# LMR514205V.net
KiCad netlist of a schematic drawn in Altium Designer
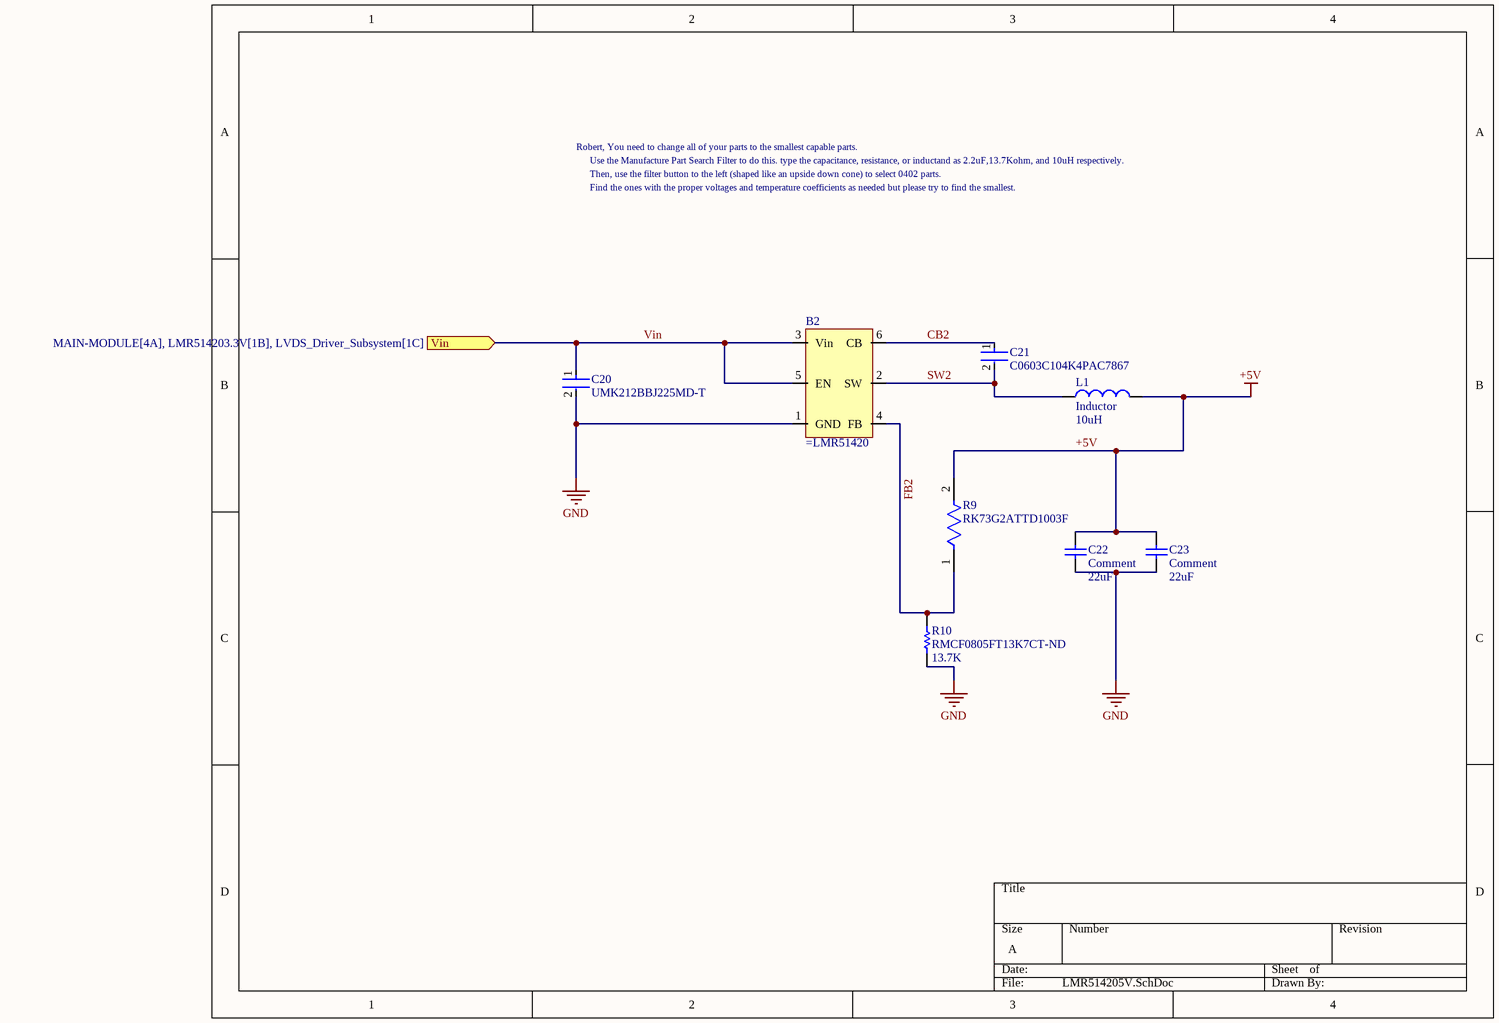
[diagram p0: LMR514205V.SchDoc]

(export (version "E")
  (design (tool "Eeschema 10.0.6"))
  (components
    (comp (ref "B2") (value "~") (footprint "LMR51420IC") (libsource (lib "LMR51420") (part "Component_1")))
    (comp (ref "C20")
      (value "UMK212BBJ225MD-T")
      (footprint "FP-0805-L_2_0_0_2-W_1_25-IPC_A")
      (description "Multilayer Ceramic Capacitor 2.2uF 50V X5R 20% SMD 0803 T/R")
      (fields (field (name "TOLERANCE") "20%"))
      (libsource (lib "Altium Content Vault") (part "02cd4be3c70576c341d710602a673aa"))
    )
    (comp (ref "C21")
      (value "C0603C104K4PAC7867")
      (footprint "CAP CER 0.1UF 16V X7R 0603")
      (description "CAP CER 0.1UF 16V X5R 0603")
      (fields
        (field (name "OCTOPART") "https://octopart.com/c0603c104k4pactu-kemet-12592163")
        (field (name "MANUFACTURER") "KEMET")
      )
      (libsource (lib "Miscellaneous Devices") (part "b4654b650e69147ec39a6b967a45e02"))
    )
    (comp (ref "C22")
      (value "Comment")
      (footprint "Cap22uF_C1206C226M4PAC7800")
      (description "Capacitor")
      (fields (field (name "ALTIUM_VALUE") "22uF") (field (name "PUBLISHER") "Altium Limited"))
      (libsource (lib "Miscellaneous Devices") (part "Cap"))
    )
    (comp (ref "C23")
      (value "Comment")
      (footprint "Cap22uF_C1206C226M4PAC7800")
      (description "Capacitor")
      (fields (field (name "ALTIUM_VALUE") "22uF") (field (name "PUBLISHER") "Altium Limited"))
      (libsource (lib "Miscellaneous Devices") (part "Cap"))
    )
    (comp (ref "L1")
      (value "Inductor")
      (footprint "MSS1246H-103MED 10uH")
      (fields (field (name "ALTIUM_VALUE") "10uH") (field (name "PUBLISHER") "Altium Limited"))
      (libsource (lib "Miscellaneous Devices") (part "Inductor"))
    )
    (comp (ref "R9")
      (value "RK73G2ATTD1003F")
      (footprint "FP-RK73G2A-IPC_A")
      (description "100kΩ ±1% 0.125W Chip Resistor 0805 Thick Film AEC-Q200 Qualified")
      (fields (field (name "TOLERANCE") "1%"))
      (libsource (lib "Altium Content Vault") (part "1029c3af85768c4190bb7ad29bc67b5"))
    )
    (comp (ref "R10")
      (value "RMCF0805FT13K7CT-ND")
      (footprint "RMCF0805FT13K7_13.7k")
      (description "Resistor")
      (fields (field (name "ALTIUM_VALUE") "13.7K") (field (name "PUBLISHER") "Altium Limited"))
      (libsource (lib "Miscellaneous Devices") (part "Res1"))
    )
  )
  (nets
    (net (code "1") (name "+5V") (class "Default")
      (node (ref "C22") (pin "2") (pinfunction "2_2") (pintype "passive"))
      (node (ref "C23") (pin "2") (pinfunction "2_2") (pintype "passive"))
      (node (ref "L1") (pin "2") (pinfunction "2_2") (pintype "passive"))
      (node (ref "R9") (pin "2") (pinfunction "2_2") (pintype "passive"))
    )
    (net (code "2") (name "/CB2") (class "Default")
      (node (ref "B2") (pin "6") (pinfunction "CB_6") (pintype "passive"))
      (node (ref "C21") (pin "1") (pinfunction "1_1") (pintype "passive"))
    )
    (net (code "3") (name "/FB2") (class "Default")
      (node (ref "B2") (pin "4") (pinfunction "FB_4") (pintype "passive"))
      (node (ref "R10") (pin "2") (pinfunction "2_2") (pintype "passive"))
      (node (ref "R9") (pin "1") (pinfunction "1_1") (pintype "passive"))
    )
    (net (code "4") (name "/SW2") (class "Default")
      (node (ref "B2") (pin "2") (pinfunction "SW_2") (pintype "passive"))
      (node (ref "C21") (pin "2") (pinfunction "2_2") (pintype "passive"))
      (node (ref "L1") (pin "1") (pinfunction "1_1") (pintype "passive"))
    )
    (net (code "5") (name "/Vin") (class "Default")
      (node (ref "B2") (pin "3") (pinfunction "Vin_3") (pintype "passive"))
      (node (ref "B2") (pin "5") (pinfunction "EN_5") (pintype "passive"))
      (node (ref "C20") (pin "1") (pinfunction "1_1") (pintype "passive"))
    )
    (net (code "6") (name "GND") (class "Default")
      (node (ref "B2") (pin "1") (pinfunction "GND_1") (pintype "passive"))
      (node (ref "C20") (pin "2") (pinfunction "2_2") (pintype "passive"))
      (node (ref "C22") (pin "1") (pinfunction "1_1") (pintype "passive"))
      (node (ref "C23") (pin "1") (pinfunction "1_1") (pintype "passive"))
      (node (ref "R10") (pin "1") (pinfunction "1_1") (pintype "passive"))
    )
  )
)
